# Brakeman.net
KiCad netlist of a schematic drawn in EAGLE
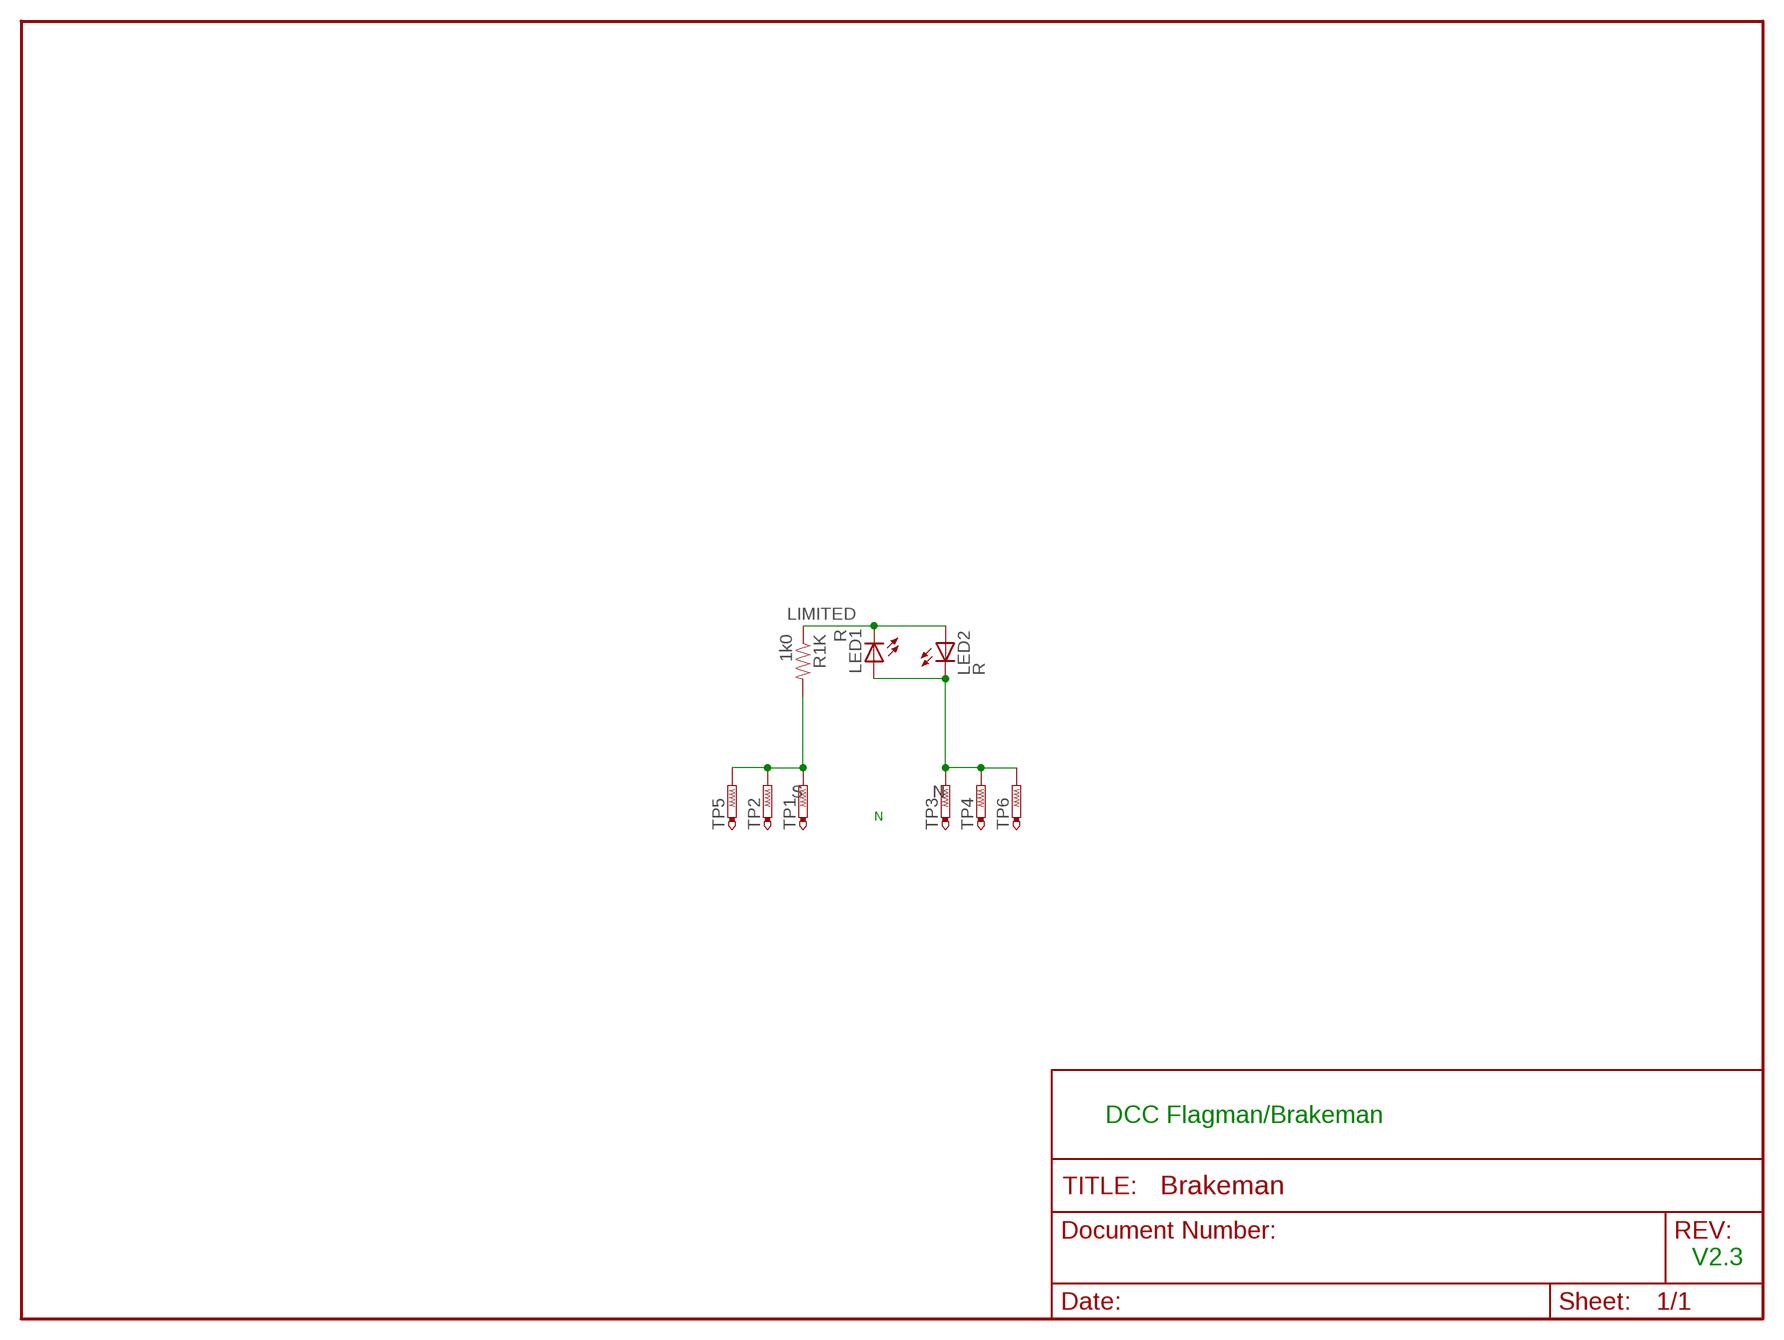
[diagram p0: schematic, sheet 1]

(export (version "E")
  (design (tool "Eeschema 10.0.6"))
  (components
    (comp (ref "LED1")
      (value "R")
      (footprint "eagle-import:0603-LED")
      (libsource (lib "eagle-import") (part "LED0603-LED"))
    )
    (comp (ref "LED2")
      (value "R")
      (footprint "eagle-import:0603-LED")
      (libsource (lib "eagle-import") (part "LED0603-LED"))
    )
    (comp (ref "R1K")
      (value "1k0")
      (footprint "eagle-import:0603-RES")
      (libsource (lib "eagle-import") (part "R0603-RES"))
    )
    (comp (ref "TP1")
      (value "PTR1PAD1-13")
      (footprint "eagle-import:P1-13")
      (libsource (lib "eagle-import") (part "PTR1PAD1-13"))
    )
    (comp (ref "TP2")
      (value "PTR1PAD1-13")
      (footprint "eagle-import:P1-13")
      (libsource (lib "eagle-import") (part "PTR1PAD1-13"))
    )
    (comp (ref "TP3")
      (value "PTR1PAD1-13")
      (footprint "eagle-import:P1-13")
      (libsource (lib "eagle-import") (part "PTR1PAD1-13"))
    )
    (comp (ref "TP4")
      (value "PTR1PAD1-13")
      (footprint "eagle-import:P1-13")
      (libsource (lib "eagle-import") (part "PTR1PAD1-13"))
    )
    (comp (ref "TP5")
      (value "PTR1PAD1-13")
      (footprint "eagle-import:P1-13")
      (libsource (lib "eagle-import") (part "PTR1PAD1-13"))
    )
    (comp (ref "TP6")
      (value "PTR1PAD1-13")
      (footprint "eagle-import:P1-13")
      (libsource (lib "eagle-import") (part "PTR1PAD1-13"))
    )
  )
  (nets
    (net (code "1") (name "/LIMITED") (class "Default")
      (node (ref "LED1") (pin "C") (pinfunction "C_C") (pintype "passive"))
      (node (ref "LED2") (pin "A") (pinfunction "A_A") (pintype "passive"))
      (node (ref "R1K") (pin "1") (pinfunction "1_1") (pintype "passive"))
    )
    (net (code "2") (name "/N") (class "Default")
      (node (ref "LED1") (pin "A") (pinfunction "A_A") (pintype "passive"))
      (node (ref "LED2") (pin "C") (pinfunction "C_C") (pintype "passive"))
      (node (ref "TP3") (pin "TP") (pinfunction "TP_TP") (pintype "input"))
      (node (ref "TP4") (pin "TP") (pinfunction "TP_TP") (pintype "input"))
      (node (ref "TP6") (pin "TP") (pinfunction "TP_TP") (pintype "input"))
    )
    (net (code "3") (name "/S") (class "Default")
      (node (ref "R1K") (pin "2") (pinfunction "2_2") (pintype "passive"))
      (node (ref "TP1") (pin "TP") (pinfunction "TP_TP") (pintype "input"))
      (node (ref "TP2") (pin "TP") (pinfunction "TP_TP") (pintype "input"))
      (node (ref "TP5") (pin "TP") (pinfunction "TP_TP") (pintype "input"))
    )
  )
)
